# Beetech_NanoEvery.net
KiCad netlist of a schematic drawn in Altium Designer
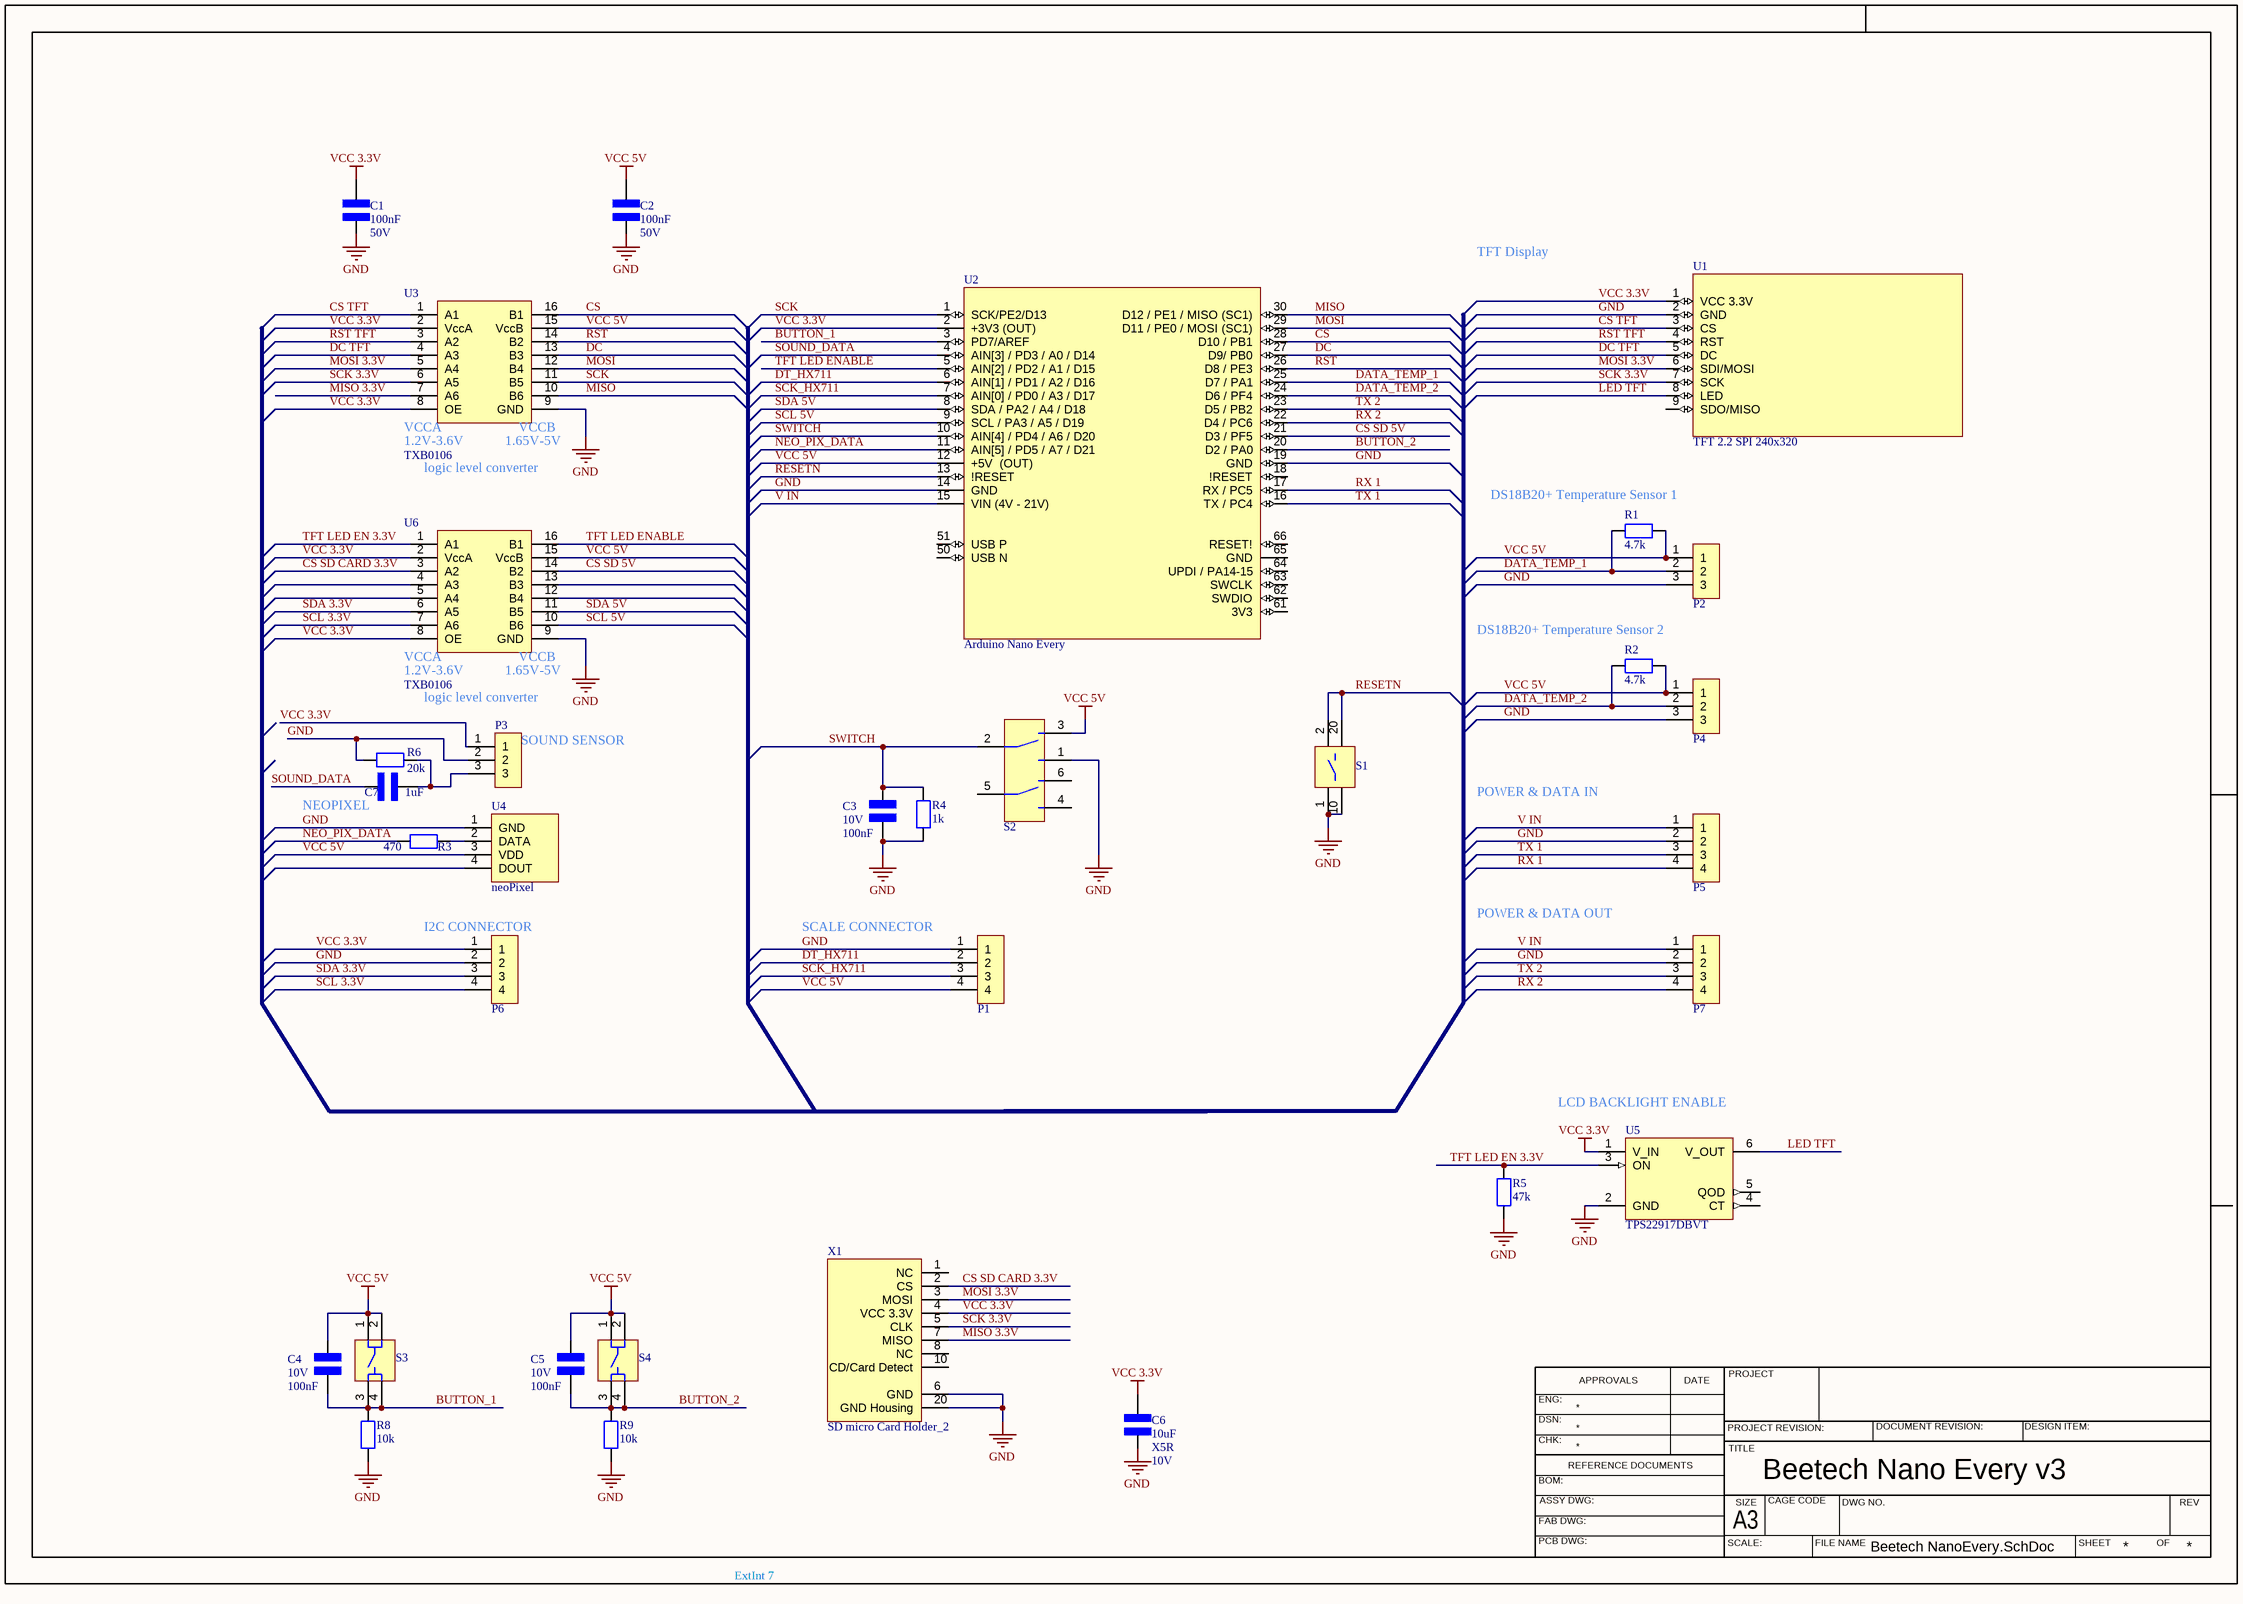
[diagram p0: Beetech NanoEvery.SchDoc]

(export (version "E")
  (design (tool "Eeschema 10.0.6"))
  (components
    (comp (ref "C1")
      (value "100nF")
      (footprint "CAP 0603")
      (description "C CERAMIC SMD")
      (fields (field (name "UMAX") "50V") (field (name "Comment") "100nF 0603_1"))
      (libsource (lib "Library CAP") (part "100nF 0603_1"))
    )
    (comp (ref "C2")
      (value "100nF")
      (footprint "CAP 0603")
      (description "C CERAMIC SMD")
      (fields (field (name "UMAX") "50V") (field (name "Comment") "100nF 0603_1"))
      (libsource (lib "Library CAP") (part "100nF 0603_1"))
    )
    (comp (ref "C3")
      (value "100nF")
      (footprint "CAP 0603")
      (description "C CERAMIC SMD")
      (fields (field (name "UMAX") "10V") (field (name "Comment") "100nF 0603"))
      (libsource (lib "Library CAP") (part "100nF 0603"))
    )
    (comp (ref "C4")
      (value "100nF")
      (footprint "CAP 0603")
      (description "C CERAMIC SMD")
      (fields (field (name "UMAX") "10V") (field (name "Comment") "100nF 0603"))
      (libsource (lib "Library CAP") (part "100nF 0603"))
    )
    (comp (ref "C5")
      (value "100nF")
      (footprint "CAP 0603")
      (description "C CERAMIC SMD")
      (fields (field (name "UMAX") "10V") (field (name "Comment") "100nF 0603"))
      (libsource (lib "Library CAP") (part "100nF 0603"))
    )
    (comp (ref "C6")
      (value "10uF")
      (footprint "CAP 0603")
      (description "C CERAMIC SMD")
      (fields
        (field (name "DIELEKTRIKUM") "X5R")
        (field (name "UMAX") "10V")
        (field (name "Comment") "10uF 0603")
      )
      (libsource (lib "Library CAP") (part "10uF 0603"))
    )
    (comp (ref "C7")
      (value "1uF")
      (footprint "CAP 0805")
      (description "C CERAMIC SMD")
      (fields (field (name "Comment") "100nF 0805"))
      (libsource (lib "Library CAP") (part "100nF 0805"))
    )
    (comp (ref "P1")
      (value "4-Pin Right Angle Housing")
      (footprint "4PIN - RND 205-EK254-2.54-04P")
      (description "4-Pin")
      (libsource (lib "Library Scematic") (part "4-Pin Screw Terminal"))
    )
    (comp (ref "P2")
      (value "3-Pin Right Angle Housing")
      (footprint "3PIN - RND 205-EK254-2.54-03P")
      (description "3-Pin")
      (libsource (lib "Library Scematic") (part "3-Pin Screw Terminal"))
    )
    (comp (ref "P3")
      (value "3-Pin Right Angle Housing")
      (footprint "3PIN - RND 205-EK254-2.54-03P")
      (description "3-Pin")
      (libsource (lib "Library Scematic") (part "3-Pin Screw Terminal"))
    )
    (comp (ref "P4")
      (value "3-Pin Right Angle Housing")
      (footprint "3PIN - RND 205-EK254-2.54-03P")
      (description "3-Pin")
      (libsource (lib "Library Scematic") (part "3-Pin Screw Terminal"))
    )
    (comp (ref "P5")
      (value "4-Pin Right Angle Housing")
      (footprint "4PIN - RND 205-EK254-2.54-04P")
      (description "4-Pin")
      (libsource (lib "Library Scematic") (part "4-Pin Screw Terminal"))
    )
    (comp (ref "P6")
      (value "4-Pin Right Angle Housing")
      (footprint "4PIN - RND 205-EK254-2.54-04P")
      (description "4-Pin")
      (libsource (lib "Library Scematic") (part "4-Pin Screw Terminal"))
    )
    (comp (ref "P7")
      (value "4-Pin Right Angle Housing")
      (footprint "4PIN - RND 205-EK254-2.54-04P")
      (description "4-Pin")
      (libsource (lib "Library Scematic") (part "4-Pin Screw Terminal"))
    )
    (comp (ref "R1")
      (value "4.7k")
      (footprint "RES 0603 FOOTPRINT")
      (description "R SMD")
      (fields (field (name "Comment") "4.7k Ohm 0603"))
      (libsource (lib "Library RES") (part "4.7k Ohm 0603"))
    )
    (comp (ref "R2")
      (value "4.7k")
      (footprint "RES 0603 FOOTPRINT")
      (description "R SMD")
      (fields (field (name "Comment") "4.7k Ohm 0603"))
      (libsource (lib "Library RES") (part "4.7k Ohm 0603"))
    )
    (comp (ref "R3")
      (value "470")
      (footprint "RES 0603 FOOTPRINT")
      (description "R SMD")
      (fields (field (name "Comment") "470 Ohm 0603"))
      (libsource (lib "Library RES") (part "470 Ohm 0603"))
    )
    (comp (ref "R4")
      (value "1k")
      (footprint "RES 0603 FOOTPRINT")
      (description "R SMD")
      (fields (field (name "Comment") "1k Ohm 0603"))
      (libsource (lib "Library RES") (part "1k Ohm 0603"))
    )
    (comp (ref "R5")
      (value "47k")
      (footprint "RES 0603 FOOTPRINT")
      (description "R SMD")
      (fields (field (name "Comment") "47k Ohm 0603"))
      (libsource (lib "Library RES") (part "47k Ohm 0603"))
    )
    (comp (ref "R6")
      (value "20k")
      (footprint "RES 0603 FOOTPRINT")
      (description "R SMD")
      (fields (field (name "Comment") "20k Ohm 0603"))
      (libsource (lib "Library RES") (part "20k Ohm 0603"))
    )
    (comp (ref "R8")
      (value "10k")
      (footprint "RES 0603 FOOTPRINT")
      (description "R SMD")
      (fields (field (name "Comment") "10k Ohm 0603"))
      (libsource (lib "Library RES") (part "10k Ohm 0603"))
    )
    (comp (ref "R9")
      (value "10k")
      (footprint "RES 0603 FOOTPRINT")
      (description "R SMD")
      (fields (field (name "Comment") "10k Ohm 0603"))
      (libsource (lib "Library RES") (part "10k Ohm 0603"))
    )
    (comp (ref "S1")
      (value "Taster Print_SMD_2")
      (footprint "Taster Print - SMD - KMR241G LFS")
      (description "Taster")
      (libsource (lib "Library Scematic") (part "Taster Print_SMD_2"))
    )
    (comp (ref "S2")
      (value "Schiebeschalter EG2207")
      (footprint "Schiebeschalter on-on 2 P, EG2207")
      (description "Schiebeschalter on-on PCM12SMTR")
      (libsource (lib "Library Scematic") (part "Schiebeschalter EG2207"))
    )
    (comp (ref "S3")
      (value "Taster Print_SMD_3")
      (footprint "Taster Print - SMD - PTS647SM70SMTR2LFS")
      (description "Taster")
      (libsource (lib "Library Scematic") (part "Taster Print_SMD_6"))
    )
    (comp (ref "S4")
      (value "Taster Print_SMD_3")
      (footprint "Taster Print - SMD - PTS647SM70SMTR2LFS")
      (description "Taster")
      (libsource (lib "Library Scematic") (part "Taster Print_SMD_6"))
    )
    (comp (ref "U1")
      (value "TFT 2.2 SPI 240x320")
      (footprint "TFT 2.2 SPI 240x320")
      (libsource (lib "Library Scematic") (part "TFT 2.2 SPI 240x320"))
    )
    (comp (ref "U2")
      (value "Arduino Nano Every")
      (footprint "Arduino Nano Every")
      (description "https://store.arduino.cc/nano-every-pack")
      (libsource (lib "Library Scematic") (part "Arduino Nano Every"))
    )
    (comp (ref "U3")
      (value "TXB0106")
      (footprint "TSSOP-16L")
      (description "Level Converter TXB0106")
      (libsource (lib "Library Scematic") (part "TXB0106 Level Converter"))
    )
    (comp (ref "U4")
      (value "neoPixel")
      (footprint "neoPixel 5050 adafruit 1655")
      (description "neoPixel 5050 adafruit 1655")
      (libsource (lib "Library Scematic") (part "neoPixel 5050 adafruit 1655"))
    )
    (comp (ref "U5")
      (value "TPS22917DBVT")
      (footprint "SOT23 - 6")
      (description "High Side Switch")
      (libsource (lib "Library Scematic") (part "TPS22917DBVT"))
    )
    (comp (ref "U6")
      (value "TXB0106")
      (footprint "TSSOP-16L")
      (description "Level Converter TXB0106")
      (libsource (lib "Library Scematic") (part "TXB0106 Level Converter"))
    )
    (comp (ref "X1")
      (value "SD micro Card Holder_2")
      (footprint "SD Card Holder - micro - 2 - sd Card inserted")
      (description "SD micro Card  Holder")
      (libsource (lib "Library Scematic") (part "SD micro Card Holder_2"))
    )
  )
  (nets
    (net (code "1") (name "/BUTTON_1") (class "Default")
      (node (ref "C4") (pin "2") (pinfunction "2_2") (pintype "passive"))
      (node (ref "R8") (pin "2") (pinfunction "2_2") (pintype "passive"))
      (node (ref "S3") (pin "3") (pinfunction "3_3") (pintype "passive"))
      (node (ref "S3") (pin "4") (pinfunction "4_4") (pintype "passive"))
      (node (ref "U2") (pin "3") (pinfunction "PD7/AREF_3") (pintype "bidirectional"))
    )
    (net (code "2") (name "/BUTTON_2") (class "Default")
      (node (ref "C5") (pin "2") (pinfunction "2_2") (pintype "passive"))
      (node (ref "R9") (pin "2") (pinfunction "2_2") (pintype "passive"))
      (node (ref "S4") (pin "3") (pinfunction "3_3") (pintype "passive"))
      (node (ref "S4") (pin "4") (pinfunction "4_4") (pintype "passive"))
      (node (ref "U2") (pin "20") (pinfunction "D2_/_PA0_20") (pintype "bidirectional"))
    )
    (net (code "3") (name "/CS") (class "Default")
      (node (ref "U2") (pin "28") (pinfunction "D10_/_PB1_28") (pintype "bidirectional"))
      (node (ref "U3") (pin "16") (pinfunction "B1_16") (pintype "passive"))
    )
    (net (code "4") (name "/CS SD 5V") (class "Default")
      (node (ref "U2") (pin "21") (pinfunction "D3_/_PF5_21") (pintype "bidirectional"))
      (node (ref "U6") (pin "14") (pinfunction "B2_14") (pintype "passive"))
    )
    (net (code "5") (name "/CS SD CARD 3.3V") (class "Default")
      (node (ref "U6") (pin "3") (pinfunction "A2_3") (pintype "passive"))
      (node (ref "X1") (pin "2") (pinfunction "CS_2") (pintype "passive"))
    )
    (net (code "6") (name "/CS TFT") (class "Default")
      (node (ref "U1") (pin "3") (pinfunction "CS_3") (pintype "bidirectional"))
      (node (ref "U3") (pin "1") (pinfunction "A1_1") (pintype "power_in"))
    )
    (net (code "7") (name "/DATA_TEMP_1") (class "Default")
      (node (ref "P2") (pin "2") (pinfunction "2_2") (pintype "passive"))
      (node (ref "R1") (pin "2") (pinfunction "2_2") (pintype "passive"))
      (node (ref "U2") (pin "25") (pinfunction "D7_/_PA1_25") (pintype "bidirectional"))
    )
    (net (code "8") (name "/DATA_TEMP_2") (class "Default")
      (node (ref "P4") (pin "2") (pinfunction "2_2") (pintype "passive"))
      (node (ref "R2") (pin "2") (pinfunction "2_2") (pintype "passive"))
      (node (ref "U2") (pin "24") (pinfunction "D6_/_PF4_24") (pintype "bidirectional"))
    )
    (net (code "9") (name "/DC") (class "Default")
      (node (ref "U2") (pin "27") (pinfunction "D9/_PB0_27") (pintype "bidirectional"))
      (node (ref "U3") (pin "13") (pinfunction "B3_13") (pintype "passive"))
    )
    (net (code "10") (name "/DC TFT") (class "Default")
      (node (ref "U1") (pin "5") (pinfunction "DC_5") (pintype "bidirectional"))
      (node (ref "U3") (pin "4") (pinfunction "A3_4") (pintype "passive"))
    )
    (net (code "11") (name "/DT_HX711") (class "Default")
      (node (ref "P1") (pin "2") (pinfunction "2_2") (pintype "passive"))
      (node (ref "U2") (pin "6") (pinfunction "AIN[1]_/_PD1_/_A2_/_D16_6") (pintype "bidirectional"))
    )
    (net (code "12") (name "/LED TFT") (class "Default")
      (node (ref "U1") (pin "8") (pinfunction "LED_8") (pintype "bidirectional"))
      (node (ref "U5") (pin "6") (pinfunction "V_OUT_6") (pintype "power_in"))
    )
    (net (code "13") (name "/MISO") (class "Default")
      (node (ref "U2") (pin "30") (pinfunction "D12_/_PE1_/_MISO_(SC1)_30") (pintype "bidirectional"))
      (node (ref "U3") (pin "10") (pinfunction "B6_10") (pintype "passive"))
    )
    (net (code "14") (name "/MISO 3.3V") (class "Default")
      (node (ref "U3") (pin "7") (pinfunction "A6_7") (pintype "passive"))
      (node (ref "X1") (pin "7") (pinfunction "MISO_7") (pintype "passive"))
    )
    (net (code "15") (name "/MOSI") (class "Default")
      (node (ref "U2") (pin "29") (pinfunction "D11_/_PE0_/_MOSI_(SC1)_29") (pintype "bidirectional"))
      (node (ref "U3") (pin "12") (pinfunction "B4_12") (pintype "passive"))
    )
    (net (code "16") (name "/MOSI 3.3V") (class "Default")
      (node (ref "U1") (pin "6") (pinfunction "SDI/MOSI_6") (pintype "bidirectional"))
      (node (ref "U3") (pin "5") (pinfunction "A4_5") (pintype "passive"))
      (node (ref "X1") (pin "3") (pinfunction "MOSI_3") (pintype "passive"))
    )
    (net (code "17") (name "/NEO_PIX_DATA") (class "Default")
      (node (ref "R3") (pin "1") (pinfunction "1_1") (pintype "passive"))
      (node (ref "U2") (pin "11") (pinfunction "AIN[5]_/_PD5_/_A7_/_D21_11") (pintype "bidirectional"))
    )
    (net (code "18") (name "/RESETN") (class "Default")
      (node (ref "S1") (pin "2") (pinfunction "2_2") (pintype "passive"))
      (node (ref "S1") (pin "20") (pinfunction "20_20") (pintype "passive"))
      (node (ref "U2") (pin "13") (pinfunction "!RESET_13") (pintype "bidirectional"))
    )
    (net (code "19") (name "/RST") (class "Default")
      (node (ref "U2") (pin "26") (pinfunction "D8_/_PE3_26") (pintype "bidirectional"))
      (node (ref "U3") (pin "14") (pinfunction "B2_14") (pintype "passive"))
    )
    (net (code "20") (name "/RST TFT") (class "Default")
      (node (ref "U1") (pin "4") (pinfunction "RST_4") (pintype "bidirectional"))
      (node (ref "U3") (pin "3") (pinfunction "A2_3") (pintype "passive"))
    )
    (net (code "21") (name "/RX 1") (class "Default")
      (node (ref "P5") (pin "4") (pinfunction "4_4") (pintype "passive"))
      (node (ref "U2") (pin "17") (pinfunction "RX_/_PC5_17") (pintype "bidirectional"))
    )
    (net (code "22") (name "/RX 2") (class "Default")
      (node (ref "P7") (pin "4") (pinfunction "4_4") (pintype "passive"))
      (node (ref "U2") (pin "22") (pinfunction "D4_/_PC6_22") (pintype "bidirectional"))
    )
    (net (code "23") (name "/SCK") (class "Default")
      (node (ref "U2") (pin "1") (pinfunction "SCK/PE2/D13_1") (pintype "bidirectional"))
      (node (ref "U3") (pin "11") (pinfunction "B5_11") (pintype "passive"))
    )
    (net (code "24") (name "/SCK 3.3V") (class "Default")
      (node (ref "U1") (pin "7") (pinfunction "SCK_7") (pintype "bidirectional"))
      (node (ref "U3") (pin "6") (pinfunction "A5_6") (pintype "passive"))
      (node (ref "X1") (pin "5") (pinfunction "CLK_5") (pintype "passive"))
    )
    (net (code "25") (name "/SCK_HX711") (class "Default")
      (node (ref "P1") (pin "3") (pinfunction "3_3") (pintype "passive"))
      (node (ref "U2") (pin "7") (pinfunction "AIN[0]_/_PD0_/_A3_/_D17_7") (pintype "bidirectional"))
    )
    (net (code "26") (name "/SCL 3.3V") (class "Default")
      (node (ref "P6") (pin "4") (pinfunction "4_4") (pintype "passive"))
      (node (ref "U6") (pin "7") (pinfunction "A6_7") (pintype "passive"))
    )
    (net (code "27") (name "/SCL 5V") (class "Default")
      (node (ref "U2") (pin "9") (pinfunction "SCL_/_PA3_/_A5_/_D19_9") (pintype "bidirectional"))
      (node (ref "U6") (pin "10") (pinfunction "B6_10") (pintype "passive"))
    )
    (net (code "28") (name "/SDA 3.3V") (class "Default")
      (node (ref "P6") (pin "3") (pinfunction "3_3") (pintype "passive"))
      (node (ref "U6") (pin "6") (pinfunction "A5_6") (pintype "passive"))
    )
    (net (code "29") (name "/SDA 5V") (class "Default")
      (node (ref "U2") (pin "8") (pinfunction "SDA_/_PA2_/_A4_/_D18_8") (pintype "bidirectional"))
      (node (ref "U6") (pin "11") (pinfunction "B5_11") (pintype "passive"))
    )
    (net (code "30") (name "/SOUND_DATA") (class "Default")
      (node (ref "C7") (pin "1") (pinfunction "1_1") (pintype "passive"))
      (node (ref "U2") (pin "4") (pinfunction "AIN[3]_/_PD3_/_A0_/_D14_4") (pintype "bidirectional"))
    )
    (net (code "31") (name "/SWITCH") (class "Default")
      (node (ref "C3") (pin "1") (pinfunction "1_1") (pintype "passive"))
      (node (ref "R4") (pin "2") (pinfunction "2_2") (pintype "passive"))
      (node (ref "S2") (pin "2") (pinfunction "2_2") (pintype "passive"))
      (node (ref "U2") (pin "10") (pinfunction "AIN[4]_/_PD4_/_A6_/_D20_10") (pintype "bidirectional"))
    )
    (net (code "32") (name "/TFT LED EN 3.3V") (class "Default")
      (node (ref "R5") (pin "2") (pinfunction "2_2") (pintype "passive"))
      (node (ref "U5") (pin "3") (pinfunction "ON_3") (pintype "input"))
      (node (ref "U6") (pin "1") (pinfunction "A1_1") (pintype "power_in"))
    )
    (net (code "33") (name "/TFT LED ENABLE") (class "Default")
      (node (ref "U2") (pin "5") (pinfunction "AIN[2]_/_PD2_/_A1_/_D15_5") (pintype "bidirectional"))
      (node (ref "U6") (pin "16") (pinfunction "B1_16") (pintype "passive"))
    )
    (net (code "34") (name "/TX 1") (class "Default")
      (node (ref "P5") (pin "3") (pinfunction "3_3") (pintype "passive"))
      (node (ref "U2") (pin "16") (pinfunction "TX_/_PC4_16") (pintype "bidirectional"))
    )
    (net (code "35") (name "/TX 2") (class "Default")
      (node (ref "P7") (pin "3") (pinfunction "3_3") (pintype "passive"))
      (node (ref "U2") (pin "23") (pinfunction "D5_/_PB2_23") (pintype "bidirectional"))
    )
    (net (code "36") (name "/V IN") (class "Default")
      (node (ref "P5") (pin "1") (pinfunction "1_1") (pintype "passive"))
      (node (ref "P7") (pin "1") (pinfunction "1_1") (pintype "passive"))
      (node (ref "U2") (pin "15") (pinfunction "VIN_(4V_-_21V)_15") (pintype "power_in"))
    )
    (net (code "37") (name "GND") (class "Default")
      (node (ref "C1") (pin "1") (pinfunction "1_1") (pintype "passive"))
      (node (ref "C2") (pin "1") (pinfunction "1_1") (pintype "passive"))
      (node (ref "C3") (pin "2") (pinfunction "2_2") (pintype "passive"))
      (node (ref "C6") (pin "1") (pinfunction "1_1") (pintype "passive"))
      (node (ref "P1") (pin "1") (pinfunction "1_1") (pintype "passive"))
      (node (ref "P2") (pin "3") (pinfunction "3_3") (pintype "passive"))
      (node (ref "P3") (pin "2") (pinfunction "2_2") (pintype "passive"))
      (node (ref "P4") (pin "3") (pinfunction "3_3") (pintype "passive"))
      (node (ref "P5") (pin "2") (pinfunction "2_2") (pintype "passive"))
      (node (ref "P6") (pin "2") (pinfunction "2_2") (pintype "passive"))
      (node (ref "P7") (pin "2") (pinfunction "2_2") (pintype "passive"))
      (node (ref "R4") (pin "1") (pinfunction "1_1") (pintype "passive"))
      (node (ref "R5") (pin "1") (pinfunction "1_1") (pintype "passive"))
      (node (ref "R6") (pin "1") (pinfunction "1_1") (pintype "passive"))
      (node (ref "R8") (pin "1") (pinfunction "1_1") (pintype "passive"))
      (node (ref "R9") (pin "1") (pinfunction "1_1") (pintype "passive"))
      (node (ref "S1") (pin "1") (pinfunction "1_1") (pintype "passive"))
      (node (ref "S1") (pin "10") (pinfunction "10_10") (pintype "passive"))
      (node (ref "S2") (pin "1") (pinfunction "1_1") (pintype "passive"))
      (node (ref "U1") (pin "2") (pinfunction "GND_2") (pintype "bidirectional"))
      (node (ref "U2") (pin "14") (pinfunction "GND_14") (pintype "power_in"))
      (node (ref "U2") (pin "19") (pinfunction "GND_19") (pintype "bidirectional"))
      (node (ref "U3") (pin "9") (pinfunction "GND_9") (pintype "passive"))
      (node (ref "U4") (pin "1") (pinfunction "GND_1") (pintype "passive"))
      (node (ref "U5") (pin "2") (pinfunction "GND_2") (pintype "power_in"))
      (node (ref "U6") (pin "9") (pinfunction "GND_9") (pintype "passive"))
      (node (ref "X1") (pin "20") (pinfunction "GND_Housing_20") (pintype "passive"))
      (node (ref "X1") (pin "6") (pinfunction "GND_6") (pintype "passive"))
    )
    (net (code "38") (name "Net-(C7-Pad2)") (class "Default")
      (node (ref "C7") (pin "2") (pinfunction "2_2") (pintype "passive"))
      (node (ref "P3") (pin "3") (pinfunction "3_3") (pintype "passive"))
      (node (ref "R6") (pin "2") (pinfunction "2_2") (pintype "passive"))
    )
    (net (code "39") (name "Net-(U4-DATA)") (class "Default")
      (node (ref "R3") (pin "2") (pinfunction "2_2") (pintype "passive"))
      (node (ref "U4") (pin "2") (pinfunction "DATA_2") (pintype "passive"))
    )
    (net (code "40") (name "VCC 3.3V") (class "Default")
      (node (ref "C1") (pin "2") (pinfunction "2_2") (pintype "passive"))
      (node (ref "C6") (pin "2") (pinfunction "2_2") (pintype "passive"))
      (node (ref "P3") (pin "1") (pinfunction "1_1") (pintype "passive"))
      (node (ref "P6") (pin "1") (pinfunction "1_1") (pintype "passive"))
      (node (ref "U1") (pin "1") (pinfunction "VCC_3.3V_1") (pintype "bidirectional"))
      (node (ref "U2") (pin "2") (pinfunction "+3V3_(OUT)_2") (pintype "power_in"))
      (node (ref "U3") (pin "2") (pinfunction "VccA_2") (pintype "passive"))
      (node (ref "U3") (pin "8") (pinfunction "OE_8") (pintype "passive"))
      (node (ref "U5") (pin "1") (pinfunction "V_IN_1") (pintype "power_in"))
      (node (ref "U6") (pin "2") (pinfunction "VccA_2") (pintype "passive"))
      (node (ref "U6") (pin "8") (pinfunction "OE_8") (pintype "passive"))
      (node (ref "X1") (pin "4") (pinfunction "VCC_3.3V_4") (pintype "passive"))
    )
    (net (code "41") (name "VCC 5V") (class "Default")
      (node (ref "C2") (pin "2") (pinfunction "2_2") (pintype "passive"))
      (node (ref "C4") (pin "1") (pinfunction "1_1") (pintype "passive"))
      (node (ref "C5") (pin "1") (pinfunction "1_1") (pintype "passive"))
      (node (ref "P1") (pin "4") (pinfunction "4_4") (pintype "passive"))
      (node (ref "P2") (pin "1") (pinfunction "1_1") (pintype "passive"))
      (node (ref "P4") (pin "1") (pinfunction "1_1") (pintype "passive"))
      (node (ref "R1") (pin "1") (pinfunction "1_1") (pintype "passive"))
      (node (ref "R2") (pin "1") (pinfunction "1_1") (pintype "passive"))
      (node (ref "S2") (pin "3") (pinfunction "3_3") (pintype "passive"))
      (node (ref "S3") (pin "1") (pinfunction "1_1") (pintype "passive"))
      (node (ref "S3") (pin "2") (pinfunction "2_2") (pintype "passive"))
      (node (ref "S4") (pin "1") (pinfunction "1_1") (pintype "passive"))
      (node (ref "S4") (pin "2") (pinfunction "2_2") (pintype "passive"))
      (node (ref "U2") (pin "12") (pinfunction "+5V__(OUT)_12") (pintype "power_in"))
      (node (ref "U3") (pin "15") (pinfunction "VccB_15") (pintype "passive"))
      (node (ref "U4") (pin "3") (pinfunction "VDD_3") (pintype "passive"))
      (node (ref "U6") (pin "15") (pinfunction "VccB_15") (pintype "passive"))
    )
    (net (code "42") (name "unconnected-(S2-Pad4)") (class "Default")
      (node (ref "S2") (pin "4") (pinfunction "4_4") (pintype "passive"))
    )
    (net (code "43") (name "unconnected-(S2-Pad5)") (class "Default")
      (node (ref "S2") (pin "5") (pinfunction "5_5") (pintype "passive"))
    )
    (net (code "44") (name "unconnected-(S2-Pad6)") (class "Default")
      (node (ref "S2") (pin "6") (pinfunction "6_6") (pintype "passive"))
    )
    (net (code "45") (name "unconnected-(U1-SDO{slash}MISO-Pad9)") (class "Default")
      (node (ref "U1") (pin "9") (pinfunction "SDO/MISO_9") (pintype "bidirectional"))
    )
    (net (code "46") (name "unconnected-(U2-!RESET-Pad18)") (class "Default")
      (node (ref "U2") (pin "18") (pinfunction "!RESET_18") (pintype "bidirectional"))
    )
    (net (code "47") (name "unconnected-(U2-3V3-Pad61)") (class "Default")
      (node (ref "U2") (pin "61") (pinfunction "3V3_61") (pintype "bidirectional"))
    )
    (net (code "48") (name "unconnected-(U2-GND-Pad65)") (class "Default")
      (node (ref "U2") (pin "65") (pinfunction "GND_65") (pintype "power_in"))
    )
    (net (code "49") (name "unconnected-(U2-RESET!-Pad66)") (class "Default")
      (node (ref "U2") (pin "66") (pinfunction "RESET!_66") (pintype "bidirectional"))
    )
    (net (code "50") (name "unconnected-(U2-SWCLK-Pad63)") (class "Default")
      (node (ref "U2") (pin "63") (pinfunction "SWCLK_63") (pintype "bidirectional"))
    )
    (net (code "51") (name "unconnected-(U2-SWDIO-Pad62)") (class "Default")
      (node (ref "U2") (pin "62") (pinfunction "SWDIO_62") (pintype "bidirectional"))
    )
    (net (code "52") (name "unconnected-(U2-UPDI_{slash}_PA14-15-Pad64)") (class "Default")
      (node (ref "U2") (pin "64") (pinfunction "UPDI_/_PA14-15_64") (pintype "bidirectional"))
    )
    (net (code "53") (name "unconnected-(U2-USB_N-Pad50)") (class "Default")
      (node (ref "U2") (pin "50") (pinfunction "USB_N_50") (pintype "bidirectional"))
    )
    (net (code "54") (name "unconnected-(U2-USB_P-Pad51)") (class "Default")
      (node (ref "U2") (pin "51") (pinfunction "USB_P_51") (pintype "bidirectional"))
    )
    (net (code "55") (name "unconnected-(U4-DOUT-Pad4)") (class "Default")
      (node (ref "U4") (pin "4") (pinfunction "DOUT_4") (pintype "passive"))
    )
    (net (code "56") (name "unconnected-(U5-CT-Pad4)") (class "Default")
      (node (ref "U5") (pin "4") (pinfunction "CT_4") (pintype "output"))
    )
    (net (code "57") (name "unconnected-(U5-QOD-Pad5)") (class "Default")
      (node (ref "U5") (pin "5") (pinfunction "QOD_5") (pintype "output"))
    )
    (net (code "58") (name "unconnected-(U6-A3-Pad4)") (class "Default")
      (node (ref "U6") (pin "4") (pinfunction "A3_4") (pintype "passive"))
    )
    (net (code "59") (name "unconnected-(U6-A4-Pad5)") (class "Default")
      (node (ref "U6") (pin "5") (pinfunction "A4_5") (pintype "passive"))
    )
    (net (code "60") (name "unconnected-(U6-B3-Pad13)") (class "Default")
      (node (ref "U6") (pin "13") (pinfunction "B3_13") (pintype "passive"))
    )
    (net (code "61") (name "unconnected-(U6-B4-Pad12)") (class "Default")
      (node (ref "U6") (pin "12") (pinfunction "B4_12") (pintype "passive"))
    )
    (net (code "62") (name "unconnected-(X1-CD{slash}Card_Detect-Pad10)") (class "Default")
      (node (ref "X1") (pin "10") (pinfunction "CD/Card_Detect_10") (pintype "passive"))
    )
    (net (code "63") (name "unconnected-(X1-NC-Pad1)") (class "Default")
      (node (ref "X1") (pin "1") (pinfunction "NC_1") (pintype "passive"))
    )
    (net (code "64") (name "unconnected-(X1-NC-Pad8)") (class "Default")
      (node (ref "X1") (pin "8") (pinfunction "NC_8") (pintype "passive"))
    )
  )
)
